# ESP8266-new.net
KiCad netlist of a schematic drawn in EAGLE
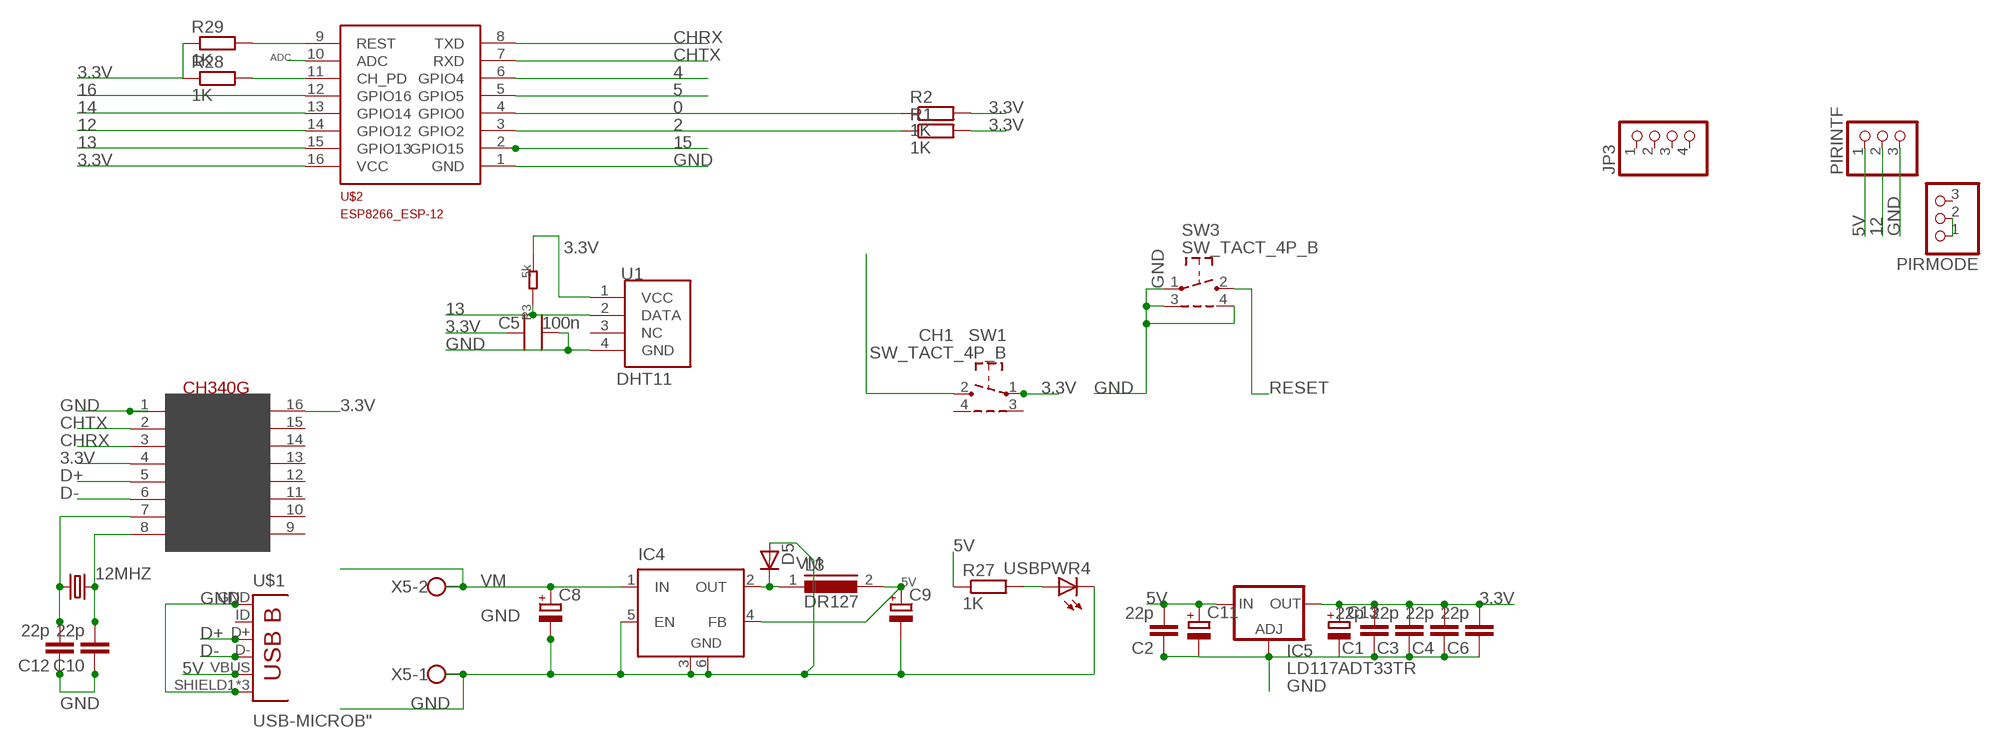
[diagram p0: schematic, sheet 1]

(export (version "E")
  (design (tool "Eeschema 10.0.6"))
  (components
    (comp (ref "12MHZ")
      (value "CRYSTALHC49UP")
      (footprint "eagle-import:HC49UP")
      (libsource (lib "eagle-import") (part "CRYSTALHC49UP"))
    )
    (comp (ref "C1")
      (value "22p")
      (footprint "eagle-import:C1206")
      (libsource (lib "eagle-import") (part "C-EUC1206"))
    )
    (comp (ref "C2")
      (value "22p")
      (footprint "eagle-import:C1206")
      (libsource (lib "eagle-import") (part "C-EUC1206"))
    )
    (comp (ref "C3")
      (value "22p")
      (footprint "eagle-import:C1206")
      (libsource (lib "eagle-import") (part "C-EUC1206"))
    )
    (comp (ref "C4")
      (value "22p")
      (footprint "eagle-import:C1206")
      (libsource (lib "eagle-import") (part "C-EUC1206"))
    )
    (comp (ref "C5")
      (value "100n")
      (footprint "eagle-import:0603")
      (libsource (lib "eagle-import") (part "C0603"))
    )
    (comp (ref "C6")
      (value "22p")
      (footprint "eagle-import:C1206")
      (libsource (lib "eagle-import") (part "C-EUC1206"))
    )
    (comp (ref "C8")
      (value "CPOL-EUE2.5-7")
      (footprint "eagle-import:E2,5-7")
      (libsource (lib "eagle-import") (part "resistor_CPOL-EUE2.5-7"))
    )
    (comp (ref "C9")
      (value "CPOL-EUE2.5-7")
      (footprint "eagle-import:E2,5-7")
      (libsource (lib "eagle-import") (part "resistor_CPOL-EUE2.5-7"))
    )
    (comp (ref "C10")
      (value "22p")
      (footprint "eagle-import:C1206")
      (libsource (lib "eagle-import") (part "C-EUC1206"))
    )
    (comp (ref "C11")
      (value "CPOL-EUC")
      (footprint "eagle-import:PANASONIC_C")
      (libsource (lib "eagle-import") (part "CPOL-EUC"))
    )
    (comp (ref "C12")
      (value "22p")
      (footprint "eagle-import:C1206")
      (libsource (lib "eagle-import") (part "C-EUC1206"))
    )
    (comp (ref "C13")
      (value "CPOL-EUC")
      (footprint "eagle-import:PANASONIC_C")
      (libsource (lib "eagle-import") (part "CPOL-EUC"))
    )
    (comp (ref "D5")
      (value "D-SOD-87")
      (footprint "eagle-import:SOD87")
      (libsource (lib "eagle-import") (part "D-SOD-87"))
    )
    (comp (ref "IC4")
      (value "LM2596S")
      (footprint "eagle-import:TO263-5")
      (libsource (lib "eagle-import") (part "LM2596S"))
    )
    (comp (ref "IC5")
      (value "LD117ADT33TR")
      (footprint "eagle-import:DPACK")
      (libsource (lib "eagle-import") (part "LD117A?DT33TR"))
    )
    (comp (ref "JP3")
      (value "PINHD-1X4/90")
      (footprint "eagle-import:1X04_90")
      (libsource (lib "eagle-import") (part "PINHD-1X4/90"))
    )
    (comp (ref "L3")
      (value "DR127")
      (footprint "eagle-import:DR127")
      (libsource (lib "eagle-import") (part "DR127"))
    )
    (comp (ref "PIRINTF")
      (value "PINHD-1X3")
      (footprint "eagle-import:1X03")
      (libsource (lib "eagle-import") (part "PINHD-1X3"))
    )
    (comp (ref "PIRMODE")
      (value "PINHD-1X3")
      (footprint "eagle-import:1X03")
      (libsource (lib "eagle-import") (part "PINHD-1X3"))
    )
    (comp (ref "R1")
      (value "1K")
      (footprint "eagle-import:M1206")
      (libsource (lib "eagle-import") (part "R-EU_M1206"))
    )
    (comp (ref "R2")
      (value "1K")
      (footprint "eagle-import:M1206")
      (libsource (lib "eagle-import") (part "R-EU_M1206"))
    )
    (comp (ref "R3")
      (value "5k")
      (footprint "eagle-import:0603")
      (libsource (lib "eagle-import") (part "R0603"))
    )
    (comp (ref "R27")
      (value "1K")
      (footprint "eagle-import:M1206")
      (libsource (lib "eagle-import") (part "R-EU_M1206"))
    )
    (comp (ref "R28")
      (value "1K")
      (footprint "eagle-import:M1206")
      (libsource (lib "eagle-import") (part "R-EU_M1206"))
    )
    (comp (ref "R29")
      (value "1K")
      (footprint "eagle-import:M1206")
      (libsource (lib "eagle-import") (part "R-EU_M1206"))
    )
    (comp (ref "SW1")
      (value "SW_TACT_4P_B")
      (footprint "eagle-import:SW_TACT_STANDARD_RIGHT_ANGLE")
      (libsource (lib "eagle-import") (part "SW_TACT_4P_B"))
    )
    (comp (ref "SW3")
      (value "SW_TACT_4P_B")
      (footprint "eagle-import:SW_TACT_STANDARD_RIGHT_ANGLE")
      (libsource (lib "eagle-import") (part "SW_TACT_4P_B"))
    )
    (comp (ref "U$1")
      (value "USB-MICROB\"")
      (footprint "eagle-import:USB-B-MICRO-SMD_V03")
      (libsource (lib "eagle-import") (part "USB-MICROB{dblquote}"))
    )
    (comp (ref "U$2")
      (value "ESP8266_ESP-12")
      (footprint "eagle-import:ESP8266-ESP12")
      (libsource (lib "eagle-import") (part "ESP8266_ESP-12"))
    )
    (comp (ref "U$4")
      (value "CH340G")
      (footprint "eagle-import:SOIC16")
      (libsource (lib "eagle-import") (part "CH340G"))
    )
    (comp (ref "U1")
      (value "DHT11")
      (footprint "eagle-import:DHT11")
      (libsource (lib "eagle-import") (part "DHT11"))
    )
    (comp (ref "USBPWR4")
      (value "LEDCHIP-LED0805")
      (footprint "eagle-import:CHIP-LED0805")
      (libsource (lib "eagle-import") (part "LEDCHIP-LED0805"))
    )
    (comp (ref "X5")
      (value "W237-102")
      (footprint "eagle-import:W237-102")
      (fields (field (name "MPN") "237-102"))
      (libsource (lib "eagle-import") (part "W237-102"))
    )
  )
  (nets
    (net (code "1") (name "/0") (class "Default")
      (node (ref "R2") (pin "1") (pinfunction "1_1") (pintype "passive"))
      (node (ref "SW1") (pin "2") (pinfunction "2_2") (pintype "passive"))
      (node (ref "U$2") (pin "4") (pinfunction "GPIO0_4") (pintype "bidirectional"))
    )
    (net (code "2") (name "/2") (class "Default")
      (node (ref "R1") (pin "1") (pinfunction "1_1") (pintype "passive"))
      (node (ref "U$2") (pin "3") (pinfunction "GPIO2_3") (pintype "bidirectional"))
    )
    (net (code "3") (name "/3.3V") (class "Default")
      (node (ref "C1") (pin "2") (pinfunction "2_2") (pintype "passive"))
      (node (ref "C13") (pin "+") (pinfunction "+_+") (pintype "passive"))
      (node (ref "C3") (pin "2") (pinfunction "2_2") (pintype "passive"))
      (node (ref "C4") (pin "2") (pinfunction "2_2") (pintype "passive"))
      (node (ref "C5") (pin "1") (pinfunction "1_1") (pintype "bidirectional"))
      (node (ref "C6") (pin "2") (pinfunction "2_2") (pintype "passive"))
      (node (ref "IC5") (pin "4") (pinfunction "OUT_4") (pintype "passive"))
      (node (ref "R1") (pin "2") (pinfunction "2_2") (pintype "passive"))
      (node (ref "R2") (pin "2") (pinfunction "2_2") (pintype "passive"))
      (node (ref "R28") (pin "1") (pinfunction "1_1") (pintype "passive"))
      (node (ref "R29") (pin "1") (pinfunction "1_1") (pintype "passive"))
      (node (ref "R3") (pin "2") (pinfunction "2_2") (pintype "bidirectional"))
      (node (ref "SW1") (pin "1") (pinfunction "1_1") (pintype "passive"))
      (node (ref "U$2") (pin "16") (pinfunction "VCC_16") (pintype "bidirectional"))
      (node (ref "U$4") (pin "16") (pinfunction "VCC_16") (pintype "bidirectional"))
      (node (ref "U$4") (pin "4") (pinfunction "V3_4") (pintype "bidirectional"))
      (node (ref "U1") (pin "1") (pinfunction "VCC_1") (pintype "bidirectional"))
    )
    (net (code "4") (name "/4") (class "Default")
      (node (ref "U$2") (pin "6") (pinfunction "GPIO4_6") (pintype "bidirectional"))
    )
    (net (code "5") (name "/5") (class "Default")
      (node (ref "U$2") (pin "5") (pinfunction "GPIO5_5") (pintype "bidirectional"))
    )
    (net (code "6") (name "/5V") (class "Default")
      (node (ref "C11") (pin "+") (pinfunction "+_+") (pintype "passive"))
      (node (ref "C2") (pin "2") (pinfunction "2_2") (pintype "passive"))
      (node (ref "C9") (pin "+") (pinfunction "+_+") (pintype "passive"))
      (node (ref "IC4") (pin "4") (pinfunction "FB_4") (pintype "input"))
      (node (ref "IC5") (pin "3") (pinfunction "IN_3") (pintype "input"))
      (node (ref "L3") (pin "2") (pinfunction "2_2") (pintype "passive"))
      (node (ref "PIRINTF") (pin "1") (pinfunction "1_1") (pintype "passive"))
      (node (ref "R27") (pin "1") (pinfunction "1_1") (pintype "passive"))
      (node (ref "U$1") (pin "VBUS") (pinfunction "VBUS_VBUS") (pintype "bidirectional"))
    )
    (net (code "7") (name "/12") (class "Default")
      (node (ref "PIRINTF") (pin "2") (pinfunction "2_2") (pintype "passive"))
      (node (ref "U$2") (pin "14") (pinfunction "GPIO12_14") (pintype "bidirectional"))
    )
    (net (code "8") (name "/13") (class "Default")
      (node (ref "R3") (pin "1") (pinfunction "1_1") (pintype "bidirectional"))
      (node (ref "U$2") (pin "15") (pinfunction "GPIO13_15") (pintype "bidirectional"))
      (node (ref "U1") (pin "2") (pinfunction "DATA_2") (pintype "bidirectional"))
    )
    (net (code "9") (name "/14") (class "Default")
      (node (ref "U$2") (pin "13") (pinfunction "GPIO14_13") (pintype "bidirectional"))
    )
    (net (code "10") (name "/15") (class "Default")
      (node (ref "U$2") (pin "2") (pinfunction "GPIO15_2") (pintype "bidirectional"))
    )
    (net (code "11") (name "/16") (class "Default")
      (node (ref "U$2") (pin "12") (pinfunction "GPIO16_12") (pintype "bidirectional"))
    )
    (net (code "12") (name "/ADC") (class "Default")
      (node (ref "U$2") (pin "10") (pinfunction "ADC_10") (pintype "bidirectional"))
    )
    (net (code "14") (name "/CHRX") (class "Default")
      (node (ref "U$2") (pin "8") (pinfunction "TXD_8") (pintype "bidirectional"))
      (node (ref "U$4") (pin "3") (pinfunction "RX_3") (pintype "bidirectional"))
    )
    (net (code "15") (name "/CHTX") (class "Default")
      (node (ref "U$2") (pin "7") (pinfunction "RXD_7") (pintype "bidirectional"))
      (node (ref "U$4") (pin "2") (pinfunction "TX_2") (pintype "bidirectional"))
    )
    (net (code "16") (name "/D+") (class "Default")
      (node (ref "U$1") (pin "D+") (pinfunction "D+_D+") (pintype "bidirectional"))
      (node (ref "U$4") (pin "5") (pinfunction "D+_5") (pintype "bidirectional"))
    )
    (net (code "17") (name "/D-") (class "Default")
      (node (ref "U$1") (pin "D-") (pinfunction "D-_D-") (pintype "bidirectional"))
      (node (ref "U$4") (pin "6") (pinfunction "D-_6") (pintype "bidirectional"))
    )
    (net (code "18") (name "/GND") (class "Default")
      (node (ref "C1") (pin "1") (pinfunction "1_1") (pintype "passive"))
      (node (ref "C10") (pin "1") (pinfunction "1_1") (pintype "passive"))
      (node (ref "C11") (pin "-") (pinfunction "-_-") (pintype "passive"))
      (node (ref "C12") (pin "1") (pinfunction "1_1") (pintype "passive"))
      (node (ref "C13") (pin "-") (pinfunction "-_-") (pintype "passive"))
      (node (ref "C2") (pin "1") (pinfunction "1_1") (pintype "passive"))
      (node (ref "C3") (pin "1") (pinfunction "1_1") (pintype "passive"))
      (node (ref "C4") (pin "1") (pinfunction "1_1") (pintype "passive"))
      (node (ref "C5") (pin "2") (pinfunction "2_2") (pintype "bidirectional"))
      (node (ref "C6") (pin "1") (pinfunction "1_1") (pintype "passive"))
      (node (ref "C8") (pin "-") (pinfunction "-_-") (pintype "passive"))
      (node (ref "C9") (pin "-") (pinfunction "-_-") (pintype "passive"))
      (node (ref "D5") (pin "2") (pinfunction "A_2") (pintype "passive"))
      (node (ref "IC4") (pin "3") (pinfunction "GND_3") (pintype "power_in"))
      (node (ref "IC4") (pin "5") (pinfunction "EN_5") (pintype "input"))
      (node (ref "IC4") (pin "6") (pinfunction "GND_6") (pintype "power_in"))
      (node (ref "IC5") (pin "1") (pinfunction "ADJ_1") (pintype "input"))
      (node (ref "PIRINTF") (pin "3") (pinfunction "3_3") (pintype "passive"))
      (node (ref "SW3") (pin "1") (pinfunction "1_1") (pintype "passive"))
      (node (ref "SW3") (pin "3") (pinfunction "3_3") (pintype "passive"))
      (node (ref "SW3") (pin "4") (pinfunction "4_4") (pintype "passive"))
      (node (ref "U$1") (pin "GND") (pinfunction "GND_GND") (pintype "bidirectional"))
      (node (ref "U$1") (pin "SHIELD1") (pinfunction "SHIELD_SHIELD1") (pintype "bidirectional"))
      (node (ref "U$1") (pin "SHIELD2") (pinfunction "SHIELD_SHIELD2") (pintype "bidirectional"))
      (node (ref "U$1") (pin "SHIELD3") (pinfunction "SHIELD_SHIELD3") (pintype "bidirectional"))
      (node (ref "U$2") (pin "1") (pinfunction "GND_1") (pintype "bidirectional"))
      (node (ref "U$4") (pin "1") (pinfunction "GND_1") (pintype "bidirectional"))
      (node (ref "U1") (pin "4") (pinfunction "GND_4") (pintype "bidirectional"))
      (node (ref "USBPWR4") (pin "C") (pinfunction "C_C") (pintype "passive"))
      (node (ref "X5") (pin "1") (pinfunction "KL_1") (pintype "passive"))
    )
    (net (code "19") (name "/RESET") (class "Default")
      (node (ref "R29") (pin "2") (pinfunction "2_2") (pintype "passive"))
      (node (ref "SW3") (pin "2") (pinfunction "2_2") (pintype "passive"))
      (node (ref "U$2") (pin "9") (pinfunction "REST_9") (pintype "bidirectional"))
    )
    (net (code "20") (name "/VM") (class "Default")
      (node (ref "C8") (pin "+") (pinfunction "+_+") (pintype "passive"))
      (node (ref "IC4") (pin "1") (pinfunction "IN_1") (pintype "input"))
      (node (ref "X5") (pin "2") (pinfunction "KL_2") (pintype "passive"))
    )
    (net (code "21") (name "Net-(D5-C)") (class "Default")
      (node (ref "D5") (pin "1") (pinfunction "C_1") (pintype "passive"))
      (node (ref "IC4") (pin "2") (pinfunction "OUT_2") (pintype "output"))
      (node (ref "L3") (pin "1") (pinfunction "1_1") (pintype "passive"))
    )
    (net (code "22") (name "Net-(PIRMODE-Pad1)") (class "Default")
      (node (ref "PIRMODE") (pin "1") (pinfunction "1_1") (pintype "passive"))
      (node (ref "PIRMODE") (pin "2") (pinfunction "2_2") (pintype "passive"))
    )
    (net (code "23") (name "Net-(R27-Pad2)") (class "Default")
      (node (ref "R27") (pin "2") (pinfunction "2_2") (pintype "passive"))
      (node (ref "USBPWR4") (pin "A") (pinfunction "A_A") (pintype "passive"))
    )
    (net (code "24") (name "Net-(U$2-CH_PD)") (class "Default")
      (node (ref "R28") (pin "2") (pinfunction "2_2") (pintype "passive"))
      (node (ref "U$2") (pin "11") (pinfunction "CH_PD_11") (pintype "bidirectional"))
    )
    (net (code "25") (name "Net-(U$4-XI)") (class "Default")
      (node (ref "12MHZ") (pin "1") (pinfunction "1_1") (pintype "passive"))
      (node (ref "C12") (pin "2") (pinfunction "2_2") (pintype "passive"))
      (node (ref "U$4") (pin "7") (pinfunction "XI_7") (pintype "bidirectional"))
    )
    (net (code "26") (name "Net-(U$4-XO)") (class "Default")
      (node (ref "12MHZ") (pin "2") (pinfunction "2_2") (pintype "passive"))
      (node (ref "C10") (pin "2") (pinfunction "2_2") (pintype "passive"))
      (node (ref "U$4") (pin "8") (pinfunction "XO_8") (pintype "bidirectional"))
    )
    (net (code "27") (name "unconnected-(JP3-Pad1)") (class "Default")
      (node (ref "JP3") (pin "1") (pinfunction "1_1") (pintype "passive"))
    )
    (net (code "28") (name "unconnected-(JP3-Pad2)") (class "Default")
      (node (ref "JP3") (pin "2") (pinfunction "2_2") (pintype "passive"))
    )
    (net (code "29") (name "unconnected-(JP3-Pad3)") (class "Default")
      (node (ref "JP3") (pin "3") (pinfunction "3_3") (pintype "passive"))
    )
    (net (code "30") (name "unconnected-(JP3-Pad4)") (class "Default")
      (node (ref "JP3") (pin "4") (pinfunction "4_4") (pintype "passive"))
    )
    (net (code "31") (name "unconnected-(PIRMODE-Pad3)") (class "Default")
      (node (ref "PIRMODE") (pin "3") (pinfunction "3_3") (pintype "passive"))
    )
    (net (code "32") (name "unconnected-(SW1-Pad3)") (class "Default")
      (node (ref "SW1") (pin "3") (pinfunction "3_3") (pintype "passive"))
    )
    (net (code "33") (name "unconnected-(SW1-Pad4)") (class "Default")
      (node (ref "SW1") (pin "4") (pinfunction "4_4") (pintype "passive"))
    )
    (net (code "34") (name "unconnected-(U$1-USBID-PadID)") (class "Default")
      (node (ref "U$1") (pin "ID") (pinfunction "USBID_ID") (pintype "bidirectional"))
    )
    (net (code "35") (name "unconnected-(U$4-CTS-Pad9)") (class "Default")
      (node (ref "U$4") (pin "9") (pinfunction "CTS_9") (pintype "bidirectional"))
    )
    (net (code "36") (name "unconnected-(U$4-DCD-Pad12)") (class "Default")
      (node (ref "U$4") (pin "12") (pinfunction "DCD_12") (pintype "bidirectional"))
    )
    (net (code "37") (name "unconnected-(U$4-DSR-Pad10)") (class "Default")
      (node (ref "U$4") (pin "10") (pinfunction "DSR_10") (pintype "bidirectional"))
    )
    (net (code "38") (name "unconnected-(U$4-DTR-Pad13)") (class "Default")
      (node (ref "U$4") (pin "13") (pinfunction "DTR_13") (pintype "bidirectional"))
    )
    (net (code "39") (name "unconnected-(U$4-RI-Pad11)") (class "Default")
      (node (ref "U$4") (pin "11") (pinfunction "RI_11") (pintype "bidirectional"))
    )
    (net (code "40") (name "unconnected-(U$4-RS232-Pad15)") (class "Default")
      (node (ref "U$4") (pin "15") (pinfunction "RS232_15") (pintype "bidirectional"))
    )
    (net (code "41") (name "unconnected-(U$4-RTS-Pad14)") (class "Default")
      (node (ref "U$4") (pin "14") (pinfunction "RTS_14") (pintype "bidirectional"))
    )
    (net (code "42") (name "unconnected-(U1-NC-Pad3)") (class "Default")
      (node (ref "U1") (pin "3") (pinfunction "NC_3") (pintype "bidirectional"))
    )
  )
)
